# UV.net
KiCad netlist of a schematic drawn in Altium Designer
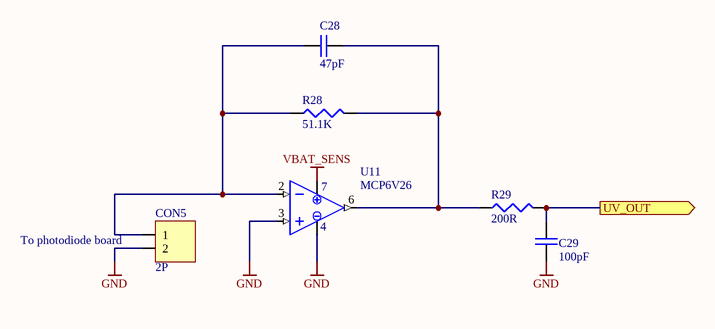
[diagram p0: UV.SchDoc]

(export (version "E")
  (design (tool "Eeschema 10.0.6"))
  (components
    (comp (ref "C28")
      (value "47pF")
      (footprint "0603")
      (description "Capacitor")
      (fields (field (name "OWNER") "Nuno Brum"))
      (libsource (lib "Alcetronics_Devices") (part "CAP"))
    )
    (comp (ref "C29")
      (value "100pF")
      (footprint "0603")
      (description "Capacitor")
      (fields (field (name "OWNER") "Nuno Brum"))
      (libsource (lib "Alcetronics_Devices") (part "CAP"))
    )
    (comp (ref "CON5")
      (value "2P")
      (footprint "INTERLOCK2-5MM-FIXED")
      (description "Connector 2 pins")
      (fields (field (name "OWNER") "Rui Rebelo"))
      (libsource (lib "Alcetronics_EM") (part "CON02"))
    )
    (comp (ref "R28")
      (value "51.1K")
      (footprint "0603")
      (description "Resistor")
      (fields (field (name "OWNER") "Nuno Brum"))
      (libsource (lib "Alcetronics_Devices") (part "RES"))
    )
    (comp (ref "R29")
      (value "200R")
      (footprint "0603")
      (description "Resistor")
      (fields (field (name "OWNER") "Nuno Brum"))
      (libsource (lib "Alcetronics_Devices") (part "RES"))
    )
    (comp (ref "U11")
      (value "MCP6V26")
      (footprint "SOIC-8")
      (description "Low-Offset Opamp")
      (libsource (lib "Alcetronics_IC") (part "MCP6V26"))
    )
  )
  (nets
    (net (code "1") (name "/UV_OUT") (class "Default")
      (node (ref "C29") (pin "2") (pinfunction "2_2") (pintype "passive"))
      (node (ref "R29") (pin "2") (pinfunction "2_2") (pintype "passive"))
    )
    (net (code "2") (name "GND") (class "Default")
      (node (ref "C29") (pin "1") (pinfunction "1_1") (pintype "passive"))
      (node (ref "CON5") (pin "2") (pinfunction "2_2") (pintype "passive"))
      (node (ref "U11") (pin "3") (pinfunction "INP_3") (pintype "input"))
      (node (ref "U11") (pin "4") (pinfunction "VSS_4") (pintype "power_in"))
    )
    (net (code "3") (name "Net-(U11-INN)") (class "Default")
      (node (ref "C28") (pin "1") (pinfunction "1_1") (pintype "passive"))
      (node (ref "CON5") (pin "1") (pinfunction "1_1") (pintype "passive"))
      (node (ref "R28") (pin "1") (pinfunction "1_1") (pintype "passive"))
      (node (ref "U11") (pin "2") (pinfunction "INN_2") (pintype "input"))
    )
    (net (code "4") (name "Net-(U11-VOUT)") (class "Default")
      (node (ref "C28") (pin "2") (pinfunction "2_2") (pintype "passive"))
      (node (ref "R28") (pin "2") (pinfunction "2_2") (pintype "passive"))
      (node (ref "R29") (pin "1") (pinfunction "1_1") (pintype "passive"))
      (node (ref "U11") (pin "6") (pinfunction "VOUT_6") (pintype "output"))
    )
    (net (code "5") (name "VBAT_SENS") (class "Default")
      (node (ref "U11") (pin "7") (pinfunction "VDD_7") (pintype "power_in"))
    )
  )
)
